# untitled.net
KiCad netlist of a schematic drawn in EAGLE
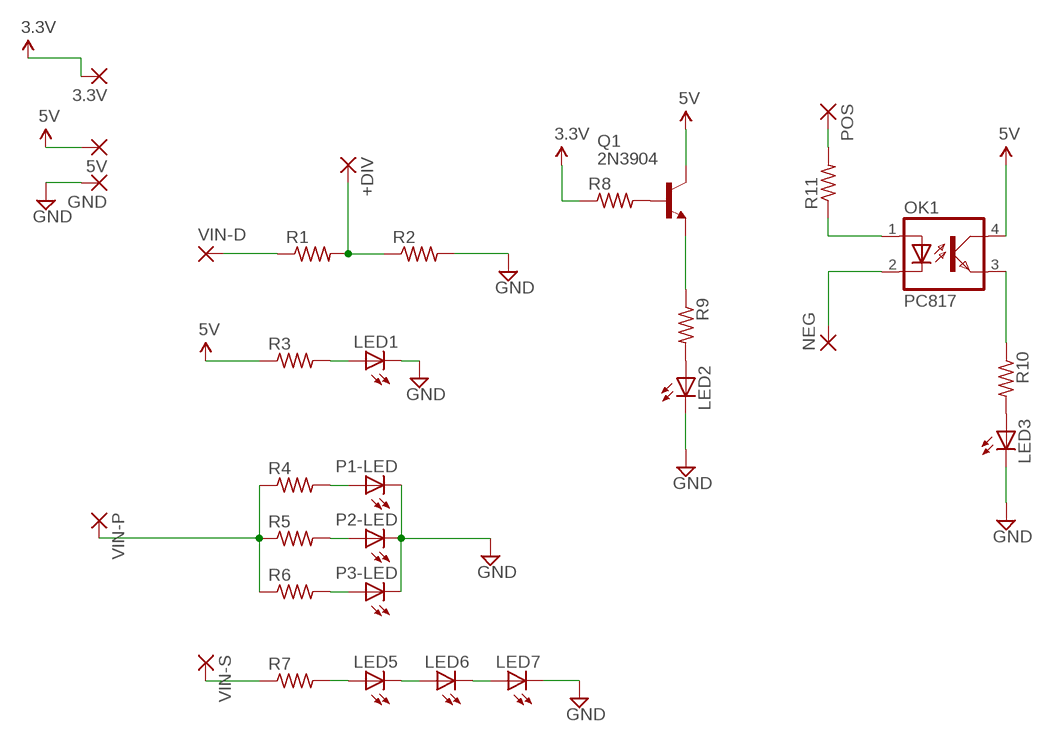
[diagram p0: schematic, sheet 1]

(export (version "E")
  (design (tool "Eeschema 10.0.6"))
  (components
    (comp (ref "+DIV")
      (value "2,54/1,0")
      (footprint "eagle-import:2,54_1,0")
      (libsource (lib "eagle-import") (part "2,54/1,0"))
    )
    (comp (ref "3.3V")
      (value "2,54/1,0")
      (footprint "eagle-import:2,54_1,0")
      (libsource (lib "eagle-import") (part "2,54/1,0"))
    )
    (comp (ref "5V")
      (value "2,54/1,0")
      (footprint "eagle-import:2,54_1,0")
      (libsource (lib "eagle-import") (part "2,54/1,0"))
    )
    (comp (ref "GND")
      (value "2,54/1,0")
      (footprint "eagle-import:2,54_1,0")
      (libsource (lib "eagle-import") (part "2,54/1,0"))
    )
    (comp (ref "LED1")
      (value "LEDCHIPLED_0805")
      (footprint "eagle-import:CHIPLED_0805")
      (libsource (lib "eagle-import") (part "LEDCHIPLED_0805"))
    )
    (comp (ref "LED2")
      (value "LEDCHIPLED_0805")
      (footprint "eagle-import:CHIPLED_0805")
      (libsource (lib "eagle-import") (part "LEDCHIPLED_0805"))
    )
    (comp (ref "LED3")
      (value "LEDCHIPLED_0805")
      (footprint "eagle-import:CHIPLED_0805")
      (libsource (lib "eagle-import") (part "LEDCHIPLED_0805"))
    )
    (comp (ref "LED5")
      (value "LEDCHIPLED_0805")
      (footprint "eagle-import:CHIPLED_0805")
      (libsource (lib "eagle-import") (part "LEDCHIPLED_0805"))
    )
    (comp (ref "LED6")
      (value "LEDCHIPLED_0805")
      (footprint "eagle-import:CHIPLED_0805")
      (libsource (lib "eagle-import") (part "LEDCHIPLED_0805"))
    )
    (comp (ref "LED7")
      (value "LEDCHIPLED_0805")
      (footprint "eagle-import:CHIPLED_0805")
      (libsource (lib "eagle-import") (part "LEDCHIPLED_0805"))
    )
    (comp (ref "NEG")
      (value "2,54/1,0")
      (footprint "eagle-import:2,54_1,0")
      (libsource (lib "eagle-import") (part "2,54/1,0"))
    )
    (comp (ref "OK1")
      (value "PC817")
      (footprint "eagle-import:DIL04")
      (fields (field (name "MPN") "PC817X4J000F"))
      (libsource (lib "eagle-import") (part "PC817"))
    )
    (comp (ref "P1-LED")
      (value "LEDCHIPLED_0805")
      (footprint "eagle-import:CHIPLED_0805")
      (libsource (lib "eagle-import") (part "LEDCHIPLED_0805"))
    )
    (comp (ref "P2-LED")
      (value "LEDCHIPLED_0805")
      (footprint "eagle-import:CHIPLED_0805")
      (libsource (lib "eagle-import") (part "LEDCHIPLED_0805"))
    )
    (comp (ref "P3-LED")
      (value "LEDCHIPLED_0805")
      (footprint "eagle-import:CHIPLED_0805")
      (libsource (lib "eagle-import") (part "LEDCHIPLED_0805"))
    )
    (comp (ref "POS")
      (value "2,54/1,0")
      (footprint "eagle-import:2,54_1,0")
      (libsource (lib "eagle-import") (part "2,54/1,0"))
    )
    (comp (ref "Q1")
      (value "2N3904")
      (footprint "eagle-import:TO92")
      (libsource (lib "eagle-import") (part "2N3904"))
    )
    (comp (ref "R1")
      (value "R-US_R0805")
      (footprint "eagle-import:R0805")
      (libsource (lib "eagle-import") (part "R-US_R0805"))
    )
    (comp (ref "R2")
      (value "R-US_R0805")
      (footprint "eagle-import:R0805")
      (libsource (lib "eagle-import") (part "R-US_R0805"))
    )
    (comp (ref "R3")
      (value "R-US_R0805")
      (footprint "eagle-import:R0805")
      (libsource (lib "eagle-import") (part "R-US_R0805"))
    )
    (comp (ref "R4")
      (value "R-US_R0805")
      (footprint "eagle-import:R0805")
      (libsource (lib "eagle-import") (part "R-US_R0805"))
    )
    (comp (ref "R5")
      (value "R-US_R0805")
      (footprint "eagle-import:R0805")
      (libsource (lib "eagle-import") (part "R-US_R0805"))
    )
    (comp (ref "R6")
      (value "R-US_R0805")
      (footprint "eagle-import:R0805")
      (libsource (lib "eagle-import") (part "R-US_R0805"))
    )
    (comp (ref "R7")
      (value "R-US_R0805")
      (footprint "eagle-import:R0805")
      (libsource (lib "eagle-import") (part "R-US_R0805"))
    )
    (comp (ref "R8")
      (value "R-US_R0805")
      (footprint "eagle-import:R0805")
      (libsource (lib "eagle-import") (part "R-US_R0805"))
    )
    (comp (ref "R9")
      (value "R-US_R0805")
      (footprint "eagle-import:R0805")
      (libsource (lib "eagle-import") (part "R-US_R0805"))
    )
    (comp (ref "R10")
      (value "R-US_R0805")
      (footprint "eagle-import:R0805")
      (libsource (lib "eagle-import") (part "R-US_R0805"))
    )
    (comp (ref "R11")
      (value "R-US_R0805")
      (footprint "eagle-import:R0805")
      (libsource (lib "eagle-import") (part "R-US_R0805"))
    )
    (comp (ref "VIN-D")
      (value "2,54/1,0")
      (footprint "eagle-import:2,54_1,0")
      (libsource (lib "eagle-import") (part "2,54/1,0"))
    )
    (comp (ref "VIN-P")
      (value "2,54/1,0")
      (footprint "eagle-import:2,54_1,0")
      (libsource (lib "eagle-import") (part "2,54/1,0"))
    )
    (comp (ref "VIN-S")
      (value "2,54/1,0")
      (footprint "eagle-import:2,54_1,0")
      (libsource (lib "eagle-import") (part "2,54/1,0"))
    )
  )
  (nets
    (net (code "1") (name "3.3V") (class "Default")
      (node (ref "3.3V") (pin "1") (pinfunction "P_1") (pintype "passive"))
      (node (ref "R8") (pin "1") (pinfunction "1_1") (pintype "passive"))
    )
    (net (code "2") (name "5V") (class "Default")
      (node (ref "5V") (pin "1") (pinfunction "P_1") (pintype "passive"))
      (node (ref "OK1") (pin "4") (pinfunction "COL_4") (pintype "passive"))
      (node (ref "Q1") (pin "1") (pinfunction "C_1") (pintype "passive"))
      (node (ref "R3") (pin "1") (pinfunction "1_1") (pintype "passive"))
    )
    (net (code "3") (name "GND") (class "Default")
      (node (ref "GND") (pin "1") (pinfunction "P_1") (pintype "passive"))
      (node (ref "LED1") (pin "C") (pinfunction "C_C") (pintype "passive"))
      (node (ref "LED2") (pin "C") (pinfunction "C_C") (pintype "passive"))
      (node (ref "LED3") (pin "C") (pinfunction "C_C") (pintype "passive"))
      (node (ref "LED7") (pin "C") (pinfunction "C_C") (pintype "passive"))
      (node (ref "P1-LED") (pin "C") (pinfunction "C_C") (pintype "passive"))
      (node (ref "P2-LED") (pin "C") (pinfunction "C_C") (pintype "passive"))
      (node (ref "P3-LED") (pin "C") (pinfunction "C_C") (pintype "passive"))
      (node (ref "R2") (pin "2") (pinfunction "2_2") (pintype "passive"))
    )
    (net (code "4") (name "Net-(+DIV-P)") (class "Default")
      (node (ref "+DIV") (pin "1") (pinfunction "P_1") (pintype "passive"))
      (node (ref "R1") (pin "2") (pinfunction "2_2") (pintype "passive"))
      (node (ref "R2") (pin "1") (pinfunction "1_1") (pintype "passive"))
    )
    (net (code "5") (name "Net-(LED1-PadA)") (class "Default")
      (node (ref "LED1") (pin "A") (pinfunction "A_A") (pintype "passive"))
      (node (ref "R3") (pin "2") (pinfunction "2_2") (pintype "passive"))
    )
    (net (code "6") (name "Net-(LED2-PadA)") (class "Default")
      (node (ref "LED2") (pin "A") (pinfunction "A_A") (pintype "passive"))
      (node (ref "R9") (pin "2") (pinfunction "2_2") (pintype "passive"))
    )
    (net (code "7") (name "Net-(LED3-PadA)") (class "Default")
      (node (ref "LED3") (pin "A") (pinfunction "A_A") (pintype "passive"))
      (node (ref "R10") (pin "2") (pinfunction "2_2") (pintype "passive"))
    )
    (net (code "8") (name "Net-(LED5-PadA)") (class "Default")
      (node (ref "LED5") (pin "A") (pinfunction "A_A") (pintype "passive"))
      (node (ref "R7") (pin "2") (pinfunction "2_2") (pintype "passive"))
    )
    (net (code "9") (name "Net-(LED5-PadC)") (class "Default")
      (node (ref "LED5") (pin "C") (pinfunction "C_C") (pintype "passive"))
      (node (ref "LED6") (pin "A") (pinfunction "A_A") (pintype "passive"))
    )
    (net (code "10") (name "Net-(LED6-PadC)") (class "Default")
      (node (ref "LED6") (pin "C") (pinfunction "C_C") (pintype "passive"))
      (node (ref "LED7") (pin "A") (pinfunction "A_A") (pintype "passive"))
    )
    (net (code "11") (name "Net-(NEG-P)") (class "Default")
      (node (ref "NEG") (pin "1") (pinfunction "P_1") (pintype "passive"))
      (node (ref "OK1") (pin "2") (pinfunction "C_2") (pintype "passive"))
    )
    (net (code "12") (name "Net-(OK1-A)") (class "Default")
      (node (ref "OK1") (pin "1") (pinfunction "A_1") (pintype "passive"))
      (node (ref "R11") (pin "1") (pinfunction "1_1") (pintype "passive"))
    )
    (net (code "13") (name "Net-(OK1-EMIT)") (class "Default")
      (node (ref "OK1") (pin "3") (pinfunction "EMIT_3") (pintype "passive"))
      (node (ref "R10") (pin "1") (pinfunction "1_1") (pintype "passive"))
    )
    (net (code "14") (name "Net-(P1-LED-PadA)") (class "Default")
      (node (ref "P1-LED") (pin "A") (pinfunction "A_A") (pintype "passive"))
      (node (ref "R4") (pin "2") (pinfunction "2_2") (pintype "passive"))
    )
    (net (code "15") (name "Net-(P2-LED-PadA)") (class "Default")
      (node (ref "P2-LED") (pin "A") (pinfunction "A_A") (pintype "passive"))
      (node (ref "R5") (pin "2") (pinfunction "2_2") (pintype "passive"))
    )
    (net (code "16") (name "Net-(P3-LED-PadA)") (class "Default")
      (node (ref "P3-LED") (pin "A") (pinfunction "A_A") (pintype "passive"))
      (node (ref "R6") (pin "2") (pinfunction "2_2") (pintype "passive"))
    )
    (net (code "17") (name "Net-(POS-P)") (class "Default")
      (node (ref "POS") (pin "1") (pinfunction "P_1") (pintype "passive"))
      (node (ref "R11") (pin "2") (pinfunction "2_2") (pintype "passive"))
    )
    (net (code "18") (name "Net-(Q1-B)") (class "Default")
      (node (ref "Q1") (pin "2") (pinfunction "B_2") (pintype "passive"))
      (node (ref "R8") (pin "2") (pinfunction "2_2") (pintype "passive"))
    )
    (net (code "19") (name "Net-(Q1-E)") (class "Default")
      (node (ref "Q1") (pin "3") (pinfunction "E_3") (pintype "passive"))
      (node (ref "R9") (pin "1") (pinfunction "1_1") (pintype "passive"))
    )
    (net (code "20") (name "Net-(VIN-D-P)") (class "Default")
      (node (ref "R1") (pin "1") (pinfunction "1_1") (pintype "passive"))
      (node (ref "VIN-D") (pin "1") (pinfunction "P_1") (pintype "passive"))
    )
    (net (code "21") (name "Net-(VIN-P-P)") (class "Default")
      (node (ref "R4") (pin "1") (pinfunction "1_1") (pintype "passive"))
      (node (ref "R5") (pin "1") (pinfunction "1_1") (pintype "passive"))
      (node (ref "R6") (pin "1") (pinfunction "1_1") (pintype "passive"))
      (node (ref "VIN-P") (pin "1") (pinfunction "P_1") (pintype "passive"))
    )
    (net (code "22") (name "Net-(VIN-S-P)") (class "Default")
      (node (ref "R7") (pin "1") (pinfunction "1_1") (pintype "passive"))
      (node (ref "VIN-S") (pin "1") (pinfunction "P_1") (pintype "passive"))
    )
  )
)
